# xmega-128a4u-switch.net
KiCad netlist of a schematic drawn in EAGLE
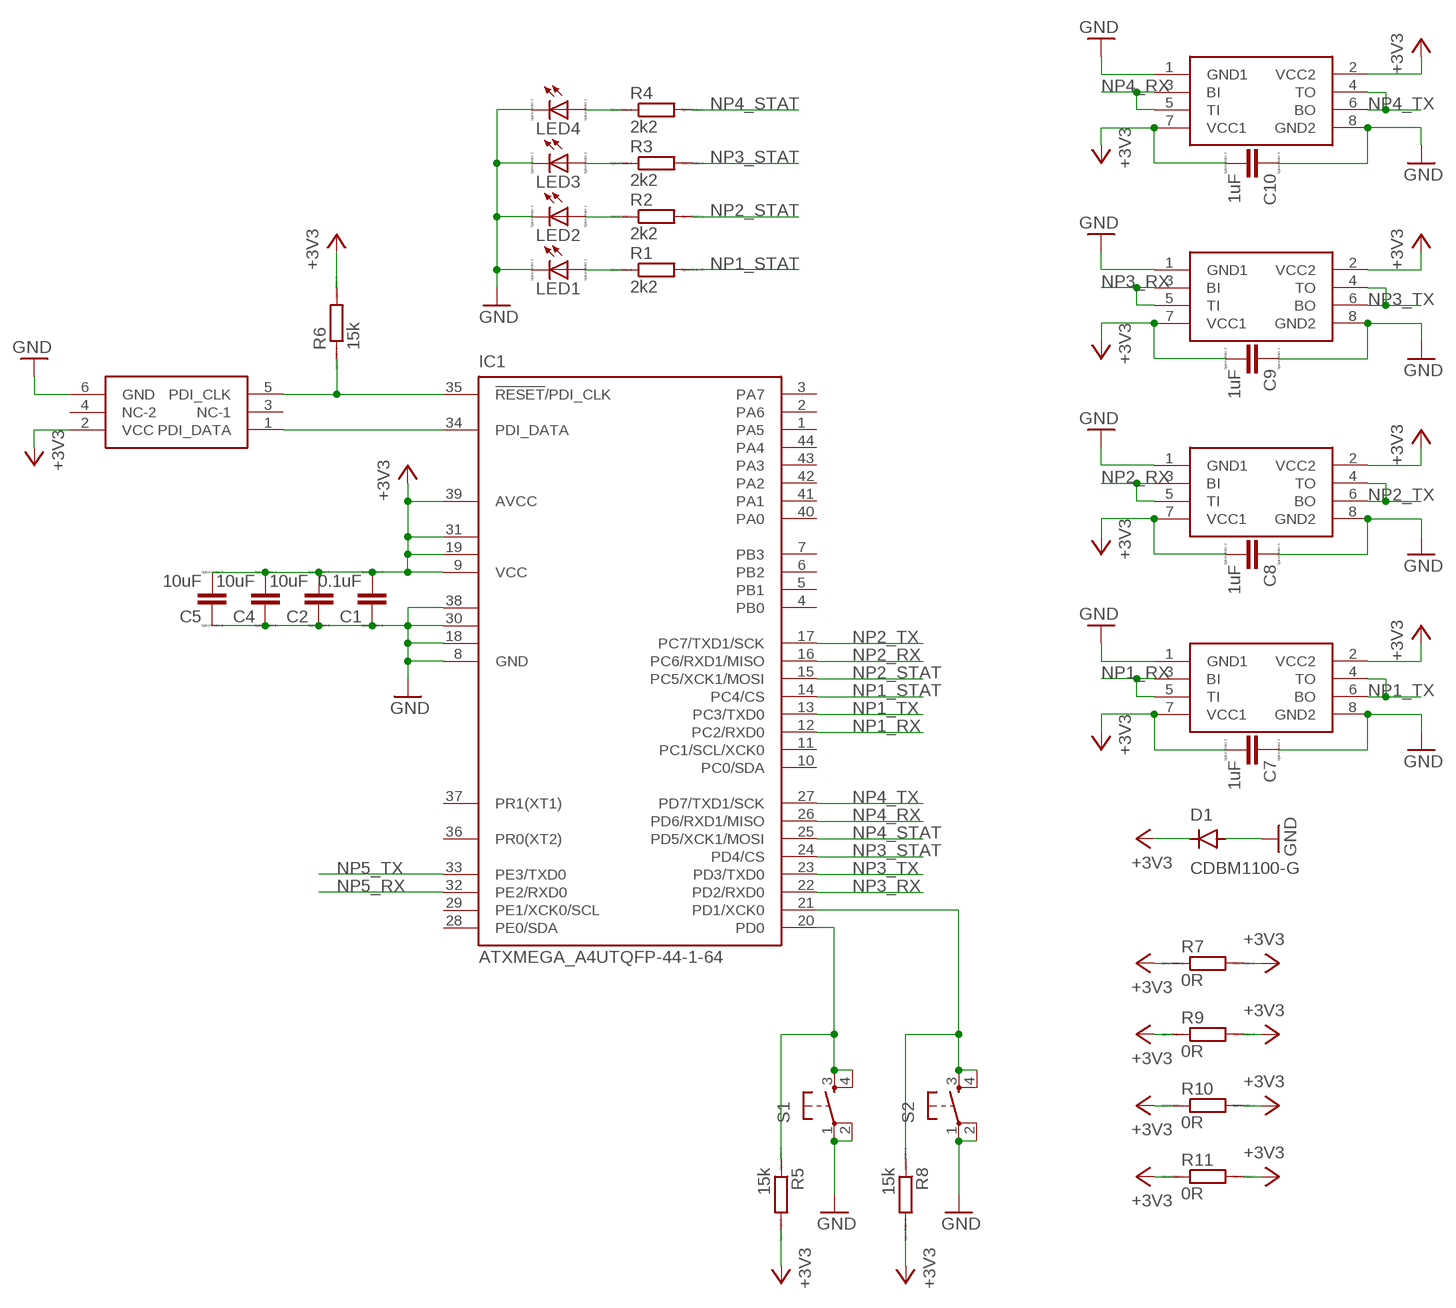
[diagram p0: schematic, sheet 1]

(export (version "E")
  (design (tool "Eeschema 10.0.6"))
  (components
    (comp (ref "C1")
      (value "0.1uF")
      (footprint "eagle-import:C0805")
      (libsource (lib "eagle-import") (part "C"))
    )
    (comp (ref "C2")
      (value "10uF")
      (footprint "eagle-import:C1206")
      (libsource (lib "eagle-import") (part "CC1206"))
    )
    (comp (ref "C4")
      (value "10uF")
      (footprint "eagle-import:C1206")
      (libsource (lib "eagle-import") (part "CC1206"))
    )
    (comp (ref "C5")
      (value "10uF")
      (footprint "eagle-import:C1206")
      (libsource (lib "eagle-import") (part "CC1206"))
    )
    (comp (ref "C7")
      (value "1uF")
      (footprint "eagle-import:C0805")
      (libsource (lib "eagle-import") (part "C"))
    )
    (comp (ref "C8")
      (value "1uF")
      (footprint "eagle-import:C0805")
      (libsource (lib "eagle-import") (part "C"))
    )
    (comp (ref "C9")
      (value "1uF")
      (footprint "eagle-import:C0805")
      (libsource (lib "eagle-import") (part "C"))
    )
    (comp (ref "C10")
      (value "1uF")
      (footprint "eagle-import:C0805")
      (libsource (lib "eagle-import") (part "C"))
    )
    (comp (ref "D1")
      (value "CDBM1100-G")
      (footprint "eagle-import:MINI-SMA")
      (libsource (lib "eagle-import") (part "CDBM1100-G"))
    )
    (comp (ref "IC1")
      (value "ATXMEGA_A4UTQFP-44-1-64")
      (footprint "eagle-import:TQFP44-13THIN")
      (libsource (lib "eagle-import") (part "ATXMEGA_A4UTQFP-44-1-64"))
    )
    (comp (ref "LED1")
      (value "LED_E")
      (footprint "eagle-import:LED_1206")
      (libsource (lib "eagle-import") (part "LED_E"))
    )
    (comp (ref "LED2")
      (value "LED_E")
      (footprint "eagle-import:LED_1206")
      (libsource (lib "eagle-import") (part "LED_E"))
    )
    (comp (ref "LED3")
      (value "LED_E")
      (footprint "eagle-import:LED_1206")
      (libsource (lib "eagle-import") (part "LED_E"))
    )
    (comp (ref "LED4")
      (value "LED_E")
      (footprint "eagle-import:LED_1206")
      (libsource (lib "eagle-import") (part "LED_E"))
    )
    (comp (ref "R1")
      (value "2k2")
      (footprint "eagle-import:R1206")
      (libsource (lib "eagle-import") (part "RR1206"))
    )
    (comp (ref "R2")
      (value "2k2")
      (footprint "eagle-import:R1206")
      (libsource (lib "eagle-import") (part "RR1206"))
    )
    (comp (ref "R3")
      (value "2k2")
      (footprint "eagle-import:R1206")
      (libsource (lib "eagle-import") (part "RR1206"))
    )
    (comp (ref "R4")
      (value "2k2")
      (footprint "eagle-import:R1206")
      (libsource (lib "eagle-import") (part "RR1206"))
    )
    (comp (ref "R5")
      (value "15k")
      (footprint "eagle-import:R0805")
      (libsource (lib "eagle-import") (part "R"))
    )
    (comp (ref "R6")
      (value "15k")
      (footprint "eagle-import:R0805")
      (libsource (lib "eagle-import") (part "R"))
    )
    (comp (ref "R7")
      (value "0R")
      (footprint "eagle-import:R1206")
      (libsource (lib "eagle-import") (part "RR1206"))
    )
    (comp (ref "R8")
      (value "15k")
      (footprint "eagle-import:R0805")
      (libsource (lib "eagle-import") (part "R"))
    )
    (comp (ref "R9")
      (value "0R")
      (footprint "eagle-import:R1206")
      (libsource (lib "eagle-import") (part "RR1206"))
    )
    (comp (ref "R10")
      (value "0R")
      (footprint "eagle-import:R1206")
      (libsource (lib "eagle-import") (part "RR1206"))
    )
    (comp (ref "R11")
      (value "0R")
      (footprint "eagle-import:R1206")
      (libsource (lib "eagle-import") (part "RR1206"))
    )
    (comp (ref "S1")
      (value "6MM_SWITCH6MM_SWITCH")
      (footprint "eagle-import:6MM_SWITCH")
      (libsource (lib "eagle-import") (part "6MM_SWITCH6MM_SWITCH"))
    )
    (comp (ref "S2")
      (value "6MM_SWITCH6MM_SWITCH")
      (footprint "eagle-import:6MM_SWITCH")
      (libsource (lib "eagle-import") (part "6MM_SWITCH6MM_SWITCH"))
    )
    (comp (ref "U$3")
      (value "NETPORT_IDC_FULLFLIP")
      (footprint "eagle-import:2X04SMD")
      (libsource (lib "eagle-import") (part "NETPORT_IDC_FULLFLIP"))
    )
    (comp (ref "U$4")
      (value "NETPORT_IDC_FULLFLIP")
      (footprint "eagle-import:2X04SMD")
      (libsource (lib "eagle-import") (part "NETPORT_IDC_FULLFLIP"))
    )
    (comp (ref "U$5")
      (value "NETPORT_IDC_FULLFLIP")
      (footprint "eagle-import:2X04SMD")
      (libsource (lib "eagle-import") (part "NETPORT_IDC_FULLFLIP"))
    )
    (comp (ref "U$6")
      (value "NETPORT_IDC_FULLFLIP")
      (footprint "eagle-import:2X04SMD")
      (libsource (lib "eagle-import") (part "NETPORT_IDC_FULLFLIP"))
    )
    (comp (ref "U$7")
      (value "PDI")
      (footprint "eagle-import:2X03SMD")
      (libsource (lib "eagle-import") (part "PDI"))
    )
  )
  (nets
    (net (code "1") (name "+3V3") (class "Default")
      (node (ref "C1") (pin "2") (pinfunction "2_2") (pintype "passive"))
      (node (ref "C10") (pin "2") (pinfunction "2_2") (pintype "passive"))
      (node (ref "C2") (pin "2") (pinfunction "2_2") (pintype "passive"))
      (node (ref "C4") (pin "2") (pinfunction "2_2") (pintype "passive"))
      (node (ref "C5") (pin "2") (pinfunction "2_2") (pintype "passive"))
      (node (ref "C7") (pin "2") (pinfunction "2_2") (pintype "passive"))
      (node (ref "C8") (pin "2") (pinfunction "2_2") (pintype "passive"))
      (node (ref "C9") (pin "2") (pinfunction "2_2") (pintype "passive"))
      (node (ref "D1") (pin "KATHODE") (pinfunction "KATHODE_KATHODE") (pintype "bidirectional"))
      (node (ref "IC1") (pin "19") (pinfunction "VCC1_19") (pintype "power_in"))
      (node (ref "IC1") (pin "31") (pinfunction "VCC2_31") (pintype "power_in"))
      (node (ref "IC1") (pin "39") (pinfunction "AVCC_39") (pintype "power_in"))
      (node (ref "IC1") (pin "9") (pinfunction "VCC_9") (pintype "power_in"))
      (node (ref "R10") (pin "1") (pinfunction "1_1") (pintype "passive"))
      (node (ref "R10") (pin "2") (pinfunction "2_2") (pintype "passive"))
      (node (ref "R11") (pin "1") (pinfunction "1_1") (pintype "passive"))
      (node (ref "R11") (pin "2") (pinfunction "2_2") (pintype "passive"))
      (node (ref "R5") (pin "2") (pinfunction "2_2") (pintype "passive"))
      (node (ref "R6") (pin "2") (pinfunction "2_2") (pintype "passive"))
      (node (ref "R7") (pin "1") (pinfunction "1_1") (pintype "passive"))
      (node (ref "R7") (pin "2") (pinfunction "2_2") (pintype "passive"))
      (node (ref "R8") (pin "2") (pinfunction "2_2") (pintype "passive"))
      (node (ref "R9") (pin "1") (pinfunction "1_1") (pintype "passive"))
      (node (ref "R9") (pin "2") (pinfunction "2_2") (pintype "passive"))
      (node (ref "U$3") (pin "2") (pinfunction "VCC2_2") (pintype "bidirectional"))
      (node (ref "U$3") (pin "7") (pinfunction "VCC1_7") (pintype "bidirectional"))
      (node (ref "U$4") (pin "2") (pinfunction "VCC2_2") (pintype "bidirectional"))
      (node (ref "U$4") (pin "7") (pinfunction "VCC1_7") (pintype "bidirectional"))
      (node (ref "U$5") (pin "2") (pinfunction "VCC2_2") (pintype "bidirectional"))
      (node (ref "U$5") (pin "7") (pinfunction "VCC1_7") (pintype "bidirectional"))
      (node (ref "U$6") (pin "2") (pinfunction "VCC2_2") (pintype "bidirectional"))
      (node (ref "U$6") (pin "7") (pinfunction "VCC1_7") (pintype "bidirectional"))
      (node (ref "U$7") (pin "2") (pinfunction "VCC_2") (pintype "bidirectional"))
    )
    (net (code "2") (name "/NP1_RX") (class "Default")
      (node (ref "IC1") (pin "12") (pinfunction "PC2/RXD0_12") (pintype "bidirectional"))
      (node (ref "U$3") (pin "3") (pinfunction "BI_3") (pintype "bidirectional"))
      (node (ref "U$3") (pin "5") (pinfunction "TI_5") (pintype "bidirectional"))
    )
    (net (code "3") (name "/NP1_STAT") (class "Default")
      (node (ref "IC1") (pin "14") (pinfunction "PC4/CS_14") (pintype "bidirectional"))
      (node (ref "R1") (pin "2") (pinfunction "2_2") (pintype "passive"))
    )
    (net (code "4") (name "/NP1_TX") (class "Default")
      (node (ref "IC1") (pin "13") (pinfunction "PC3/TXD0_13") (pintype "bidirectional"))
      (node (ref "U$3") (pin "4") (pinfunction "TO_4") (pintype "bidirectional"))
      (node (ref "U$3") (pin "6") (pinfunction "BO_6") (pintype "bidirectional"))
    )
    (net (code "5") (name "/NP2_RX") (class "Default")
      (node (ref "IC1") (pin "16") (pinfunction "PC6/RXD1/MISO_16") (pintype "bidirectional"))
      (node (ref "U$4") (pin "3") (pinfunction "BI_3") (pintype "bidirectional"))
      (node (ref "U$4") (pin "5") (pinfunction "TI_5") (pintype "bidirectional"))
    )
    (net (code "6") (name "/NP2_STAT") (class "Default")
      (node (ref "IC1") (pin "15") (pinfunction "PC5/XCK1/MOSI_15") (pintype "bidirectional"))
      (node (ref "R2") (pin "2") (pinfunction "2_2") (pintype "passive"))
    )
    (net (code "7") (name "/NP2_TX") (class "Default")
      (node (ref "IC1") (pin "17") (pinfunction "PC7/TXD1/SCK_17") (pintype "bidirectional"))
      (node (ref "U$4") (pin "4") (pinfunction "TO_4") (pintype "bidirectional"))
      (node (ref "U$4") (pin "6") (pinfunction "BO_6") (pintype "bidirectional"))
    )
    (net (code "8") (name "/NP3_RX") (class "Default")
      (node (ref "IC1") (pin "22") (pinfunction "PD2/RXD0_22") (pintype "bidirectional"))
      (node (ref "U$5") (pin "3") (pinfunction "BI_3") (pintype "bidirectional"))
      (node (ref "U$5") (pin "5") (pinfunction "TI_5") (pintype "bidirectional"))
    )
    (net (code "9") (name "/NP3_STAT") (class "Default")
      (node (ref "IC1") (pin "24") (pinfunction "PD4/CS_24") (pintype "bidirectional"))
      (node (ref "R3") (pin "2") (pinfunction "2_2") (pintype "passive"))
    )
    (net (code "10") (name "/NP3_TX") (class "Default")
      (node (ref "IC1") (pin "23") (pinfunction "PD3/TXD0_23") (pintype "bidirectional"))
      (node (ref "U$5") (pin "4") (pinfunction "TO_4") (pintype "bidirectional"))
      (node (ref "U$5") (pin "6") (pinfunction "BO_6") (pintype "bidirectional"))
    )
    (net (code "11") (name "/NP4_RX") (class "Default")
      (node (ref "IC1") (pin "26") (pinfunction "PD6/RXD1/MISO_26") (pintype "bidirectional"))
      (node (ref "U$6") (pin "3") (pinfunction "BI_3") (pintype "bidirectional"))
      (node (ref "U$6") (pin "5") (pinfunction "TI_5") (pintype "bidirectional"))
    )
    (net (code "12") (name "/NP4_STAT") (class "Default")
      (node (ref "IC1") (pin "25") (pinfunction "PD5/XCK1/MOSI_25") (pintype "bidirectional"))
      (node (ref "R4") (pin "2") (pinfunction "2_2") (pintype "passive"))
    )
    (net (code "13") (name "/NP4_TX") (class "Default")
      (node (ref "IC1") (pin "27") (pinfunction "PD7/TXD1/SCK_27") (pintype "bidirectional"))
      (node (ref "U$6") (pin "4") (pinfunction "TO_4") (pintype "bidirectional"))
      (node (ref "U$6") (pin "6") (pinfunction "BO_6") (pintype "bidirectional"))
    )
    (net (code "14") (name "/NP5_RX") (class "Default")
      (node (ref "IC1") (pin "32") (pinfunction "PE2/RXD0_32") (pintype "bidirectional"))
    )
    (net (code "15") (name "/NP5_TX") (class "Default")
      (node (ref "IC1") (pin "33") (pinfunction "PE3/TXD0_33") (pintype "bidirectional"))
    )
    (net (code "16") (name "GND") (class "Default")
      (node (ref "C1") (pin "1") (pinfunction "1_1") (pintype "passive"))
      (node (ref "C10") (pin "1") (pinfunction "1_1") (pintype "passive"))
      (node (ref "C2") (pin "1") (pinfunction "1_1") (pintype "passive"))
      (node (ref "C4") (pin "1") (pinfunction "1_1") (pintype "passive"))
      (node (ref "C5") (pin "1") (pinfunction "1_1") (pintype "passive"))
      (node (ref "C7") (pin "1") (pinfunction "1_1") (pintype "passive"))
      (node (ref "C8") (pin "1") (pinfunction "1_1") (pintype "passive"))
      (node (ref "C9") (pin "1") (pinfunction "1_1") (pintype "passive"))
      (node (ref "D1") (pin "ANODE") (pinfunction "ANODE_ANODE") (pintype "bidirectional"))
      (node (ref "IC1") (pin "18") (pinfunction "GND1_18") (pintype "power_in"))
      (node (ref "IC1") (pin "30") (pinfunction "GND2_30") (pintype "power_in"))
      (node (ref "IC1") (pin "38") (pinfunction "GND3_38") (pintype "power_in"))
      (node (ref "IC1") (pin "8") (pinfunction "GND_8") (pintype "power_in"))
      (node (ref "LED1") (pin "C") (pinfunction "C_C") (pintype "passive"))
      (node (ref "LED2") (pin "C") (pinfunction "C_C") (pintype "passive"))
      (node (ref "LED3") (pin "C") (pinfunction "C_C") (pintype "passive"))
      (node (ref "LED4") (pin "C") (pinfunction "C_C") (pintype "passive"))
      (node (ref "S1") (pin "1") (pinfunction "P_1") (pintype "passive"))
      (node (ref "S1") (pin "2") (pinfunction "P1_2") (pintype "passive"))
      (node (ref "S2") (pin "1") (pinfunction "P_1") (pintype "passive"))
      (node (ref "S2") (pin "2") (pinfunction "P1_2") (pintype "passive"))
      (node (ref "U$3") (pin "1") (pinfunction "GND1_1") (pintype "bidirectional"))
      (node (ref "U$3") (pin "8") (pinfunction "GND2_8") (pintype "bidirectional"))
      (node (ref "U$4") (pin "1") (pinfunction "GND1_1") (pintype "bidirectional"))
      (node (ref "U$4") (pin "8") (pinfunction "GND2_8") (pintype "bidirectional"))
      (node (ref "U$5") (pin "1") (pinfunction "GND1_1") (pintype "bidirectional"))
      (node (ref "U$5") (pin "8") (pinfunction "GND2_8") (pintype "bidirectional"))
      (node (ref "U$6") (pin "1") (pinfunction "GND1_1") (pintype "bidirectional"))
      (node (ref "U$6") (pin "8") (pinfunction "GND2_8") (pintype "bidirectional"))
      (node (ref "U$7") (pin "6") (pinfunction "GND_6") (pintype "bidirectional"))
    )
    (net (code "17") (name "Net-(IC1-PD0)") (class "Default")
      (node (ref "IC1") (pin "20") (pinfunction "PD0_20") (pintype "bidirectional"))
      (node (ref "R5") (pin "1") (pinfunction "1_1") (pintype "passive"))
      (node (ref "S1") (pin "3") (pinfunction "S_3") (pintype "passive"))
      (node (ref "S1") (pin "4") (pinfunction "S1_4") (pintype "passive"))
    )
    (net (code "18") (name "Net-(IC1-PD1{slash}XCK0)") (class "Default")
      (node (ref "IC1") (pin "21") (pinfunction "PD1/XCK0_21") (pintype "bidirectional"))
      (node (ref "R8") (pin "1") (pinfunction "1_1") (pintype "passive"))
      (node (ref "S2") (pin "3") (pinfunction "S_3") (pintype "passive"))
      (node (ref "S2") (pin "4") (pinfunction "S1_4") (pintype "passive"))
    )
    (net (code "19") (name "Net-(IC1-PDI_DATA)") (class "Default")
      (node (ref "IC1") (pin "34") (pinfunction "PDI_DATA_34") (pintype "bidirectional"))
      (node (ref "U$7") (pin "1") (pinfunction "PDI_DATA_1") (pintype "bidirectional"))
    )
    (net (code "20") (name "Net-(IC1-~{RESET}{slash}PDI_CLK)") (class "Default")
      (node (ref "IC1") (pin "35") (pinfunction "~{RESET}/PDI_CLK_35") (pintype "bidirectional"))
      (node (ref "R6") (pin "1") (pinfunction "1_1") (pintype "passive"))
      (node (ref "U$7") (pin "5") (pinfunction "PDI_CLK_5") (pintype "bidirectional"))
    )
    (net (code "21") (name "Net-(LED1-PadA)") (class "Default")
      (node (ref "LED1") (pin "A") (pinfunction "A_A") (pintype "passive"))
      (node (ref "R1") (pin "1") (pinfunction "1_1") (pintype "passive"))
    )
    (net (code "22") (name "Net-(LED2-PadA)") (class "Default")
      (node (ref "LED2") (pin "A") (pinfunction "A_A") (pintype "passive"))
      (node (ref "R2") (pin "1") (pinfunction "1_1") (pintype "passive"))
    )
    (net (code "23") (name "Net-(LED3-PadA)") (class "Default")
      (node (ref "LED3") (pin "A") (pinfunction "A_A") (pintype "passive"))
      (node (ref "R3") (pin "1") (pinfunction "1_1") (pintype "passive"))
    )
    (net (code "24") (name "Net-(LED4-PadA)") (class "Default")
      (node (ref "LED4") (pin "A") (pinfunction "A_A") (pintype "passive"))
      (node (ref "R4") (pin "1") (pinfunction "1_1") (pintype "passive"))
    )
    (net (code "25") (name "unconnected-(IC1-PA0-Pad40)") (class "Default")
      (node (ref "IC1") (pin "40") (pinfunction "PA0_40") (pintype "bidirectional"))
    )
    (net (code "26") (name "unconnected-(IC1-PA1-Pad41)") (class "Default")
      (node (ref "IC1") (pin "41") (pinfunction "PA1_41") (pintype "bidirectional"))
    )
    (net (code "27") (name "unconnected-(IC1-PA2-Pad42)") (class "Default")
      (node (ref "IC1") (pin "42") (pinfunction "PA2_42") (pintype "bidirectional"))
    )
    (net (code "28") (name "unconnected-(IC1-PA3-Pad43)") (class "Default")
      (node (ref "IC1") (pin "43") (pinfunction "PA3_43") (pintype "bidirectional"))
    )
    (net (code "29") (name "unconnected-(IC1-PA4-Pad44)") (class "Default")
      (node (ref "IC1") (pin "44") (pinfunction "PA4_44") (pintype "bidirectional"))
    )
    (net (code "30") (name "unconnected-(IC1-PA5-Pad1)") (class "Default")
      (node (ref "IC1") (pin "1") (pinfunction "PA5_1") (pintype "bidirectional"))
    )
    (net (code "31") (name "unconnected-(IC1-PA6-Pad2)") (class "Default")
      (node (ref "IC1") (pin "2") (pinfunction "PA6_2") (pintype "bidirectional"))
    )
    (net (code "32") (name "unconnected-(IC1-PA7-Pad3)") (class "Default")
      (node (ref "IC1") (pin "3") (pinfunction "PA7_3") (pintype "bidirectional"))
    )
    (net (code "33") (name "unconnected-(IC1-PB0-Pad4)") (class "Default")
      (node (ref "IC1") (pin "4") (pinfunction "PB0_4") (pintype "bidirectional"))
    )
    (net (code "34") (name "unconnected-(IC1-PB1-Pad5)") (class "Default")
      (node (ref "IC1") (pin "5") (pinfunction "PB1_5") (pintype "bidirectional"))
    )
    (net (code "35") (name "unconnected-(IC1-PB2-Pad6)") (class "Default")
      (node (ref "IC1") (pin "6") (pinfunction "PB2_6") (pintype "bidirectional"))
    )
    (net (code "36") (name "unconnected-(IC1-PB3-Pad7)") (class "Default")
      (node (ref "IC1") (pin "7") (pinfunction "PB3_7") (pintype "bidirectional"))
    )
    (net (code "37") (name "unconnected-(IC1-PC0{slash}SDA-Pad10)") (class "Default")
      (node (ref "IC1") (pin "10") (pinfunction "PC0/SDA_10") (pintype "bidirectional"))
    )
    (net (code "38") (name "unconnected-(IC1-PC1{slash}SCL{slash}XCK0-Pad11)") (class "Default")
      (node (ref "IC1") (pin "11") (pinfunction "PC1/SCL/XCK0_11") (pintype "bidirectional"))
    )
    (net (code "39") (name "unconnected-(IC1-PE0{slash}SDA-Pad28)") (class "Default")
      (node (ref "IC1") (pin "28") (pinfunction "PE0/SDA_28") (pintype "bidirectional"))
    )
    (net (code "40") (name "unconnected-(IC1-PE1{slash}XCK0{slash}SCL-Pad29)") (class "Default")
      (node (ref "IC1") (pin "29") (pinfunction "PE1/XCK0/SCL_29") (pintype "bidirectional"))
    )
    (net (code "41") (name "unconnected-(IC1-PR0(XT2)-Pad36)") (class "Default")
      (node (ref "IC1") (pin "36") (pinfunction "PR0(XT2)_36") (pintype "bidirectional"))
    )
    (net (code "42") (name "unconnected-(IC1-PR1(XT1)-Pad37)") (class "Default")
      (node (ref "IC1") (pin "37") (pinfunction "PR1(XT1)_37") (pintype "bidirectional"))
    )
    (net (code "43") (name "unconnected-(U$7-NC-1-Pad3)") (class "Default")
      (node (ref "U$7") (pin "3") (pinfunction "NC-1_3") (pintype "bidirectional"))
    )
    (net (code "44") (name "unconnected-(U$7-NC-2-Pad4)") (class "Default")
      (node (ref "U$7") (pin "4") (pinfunction "NC-2_4") (pintype "bidirectional"))
    )
  )
)
